# controller_board.net
KiCad netlist of a schematic drawn in EAGLE
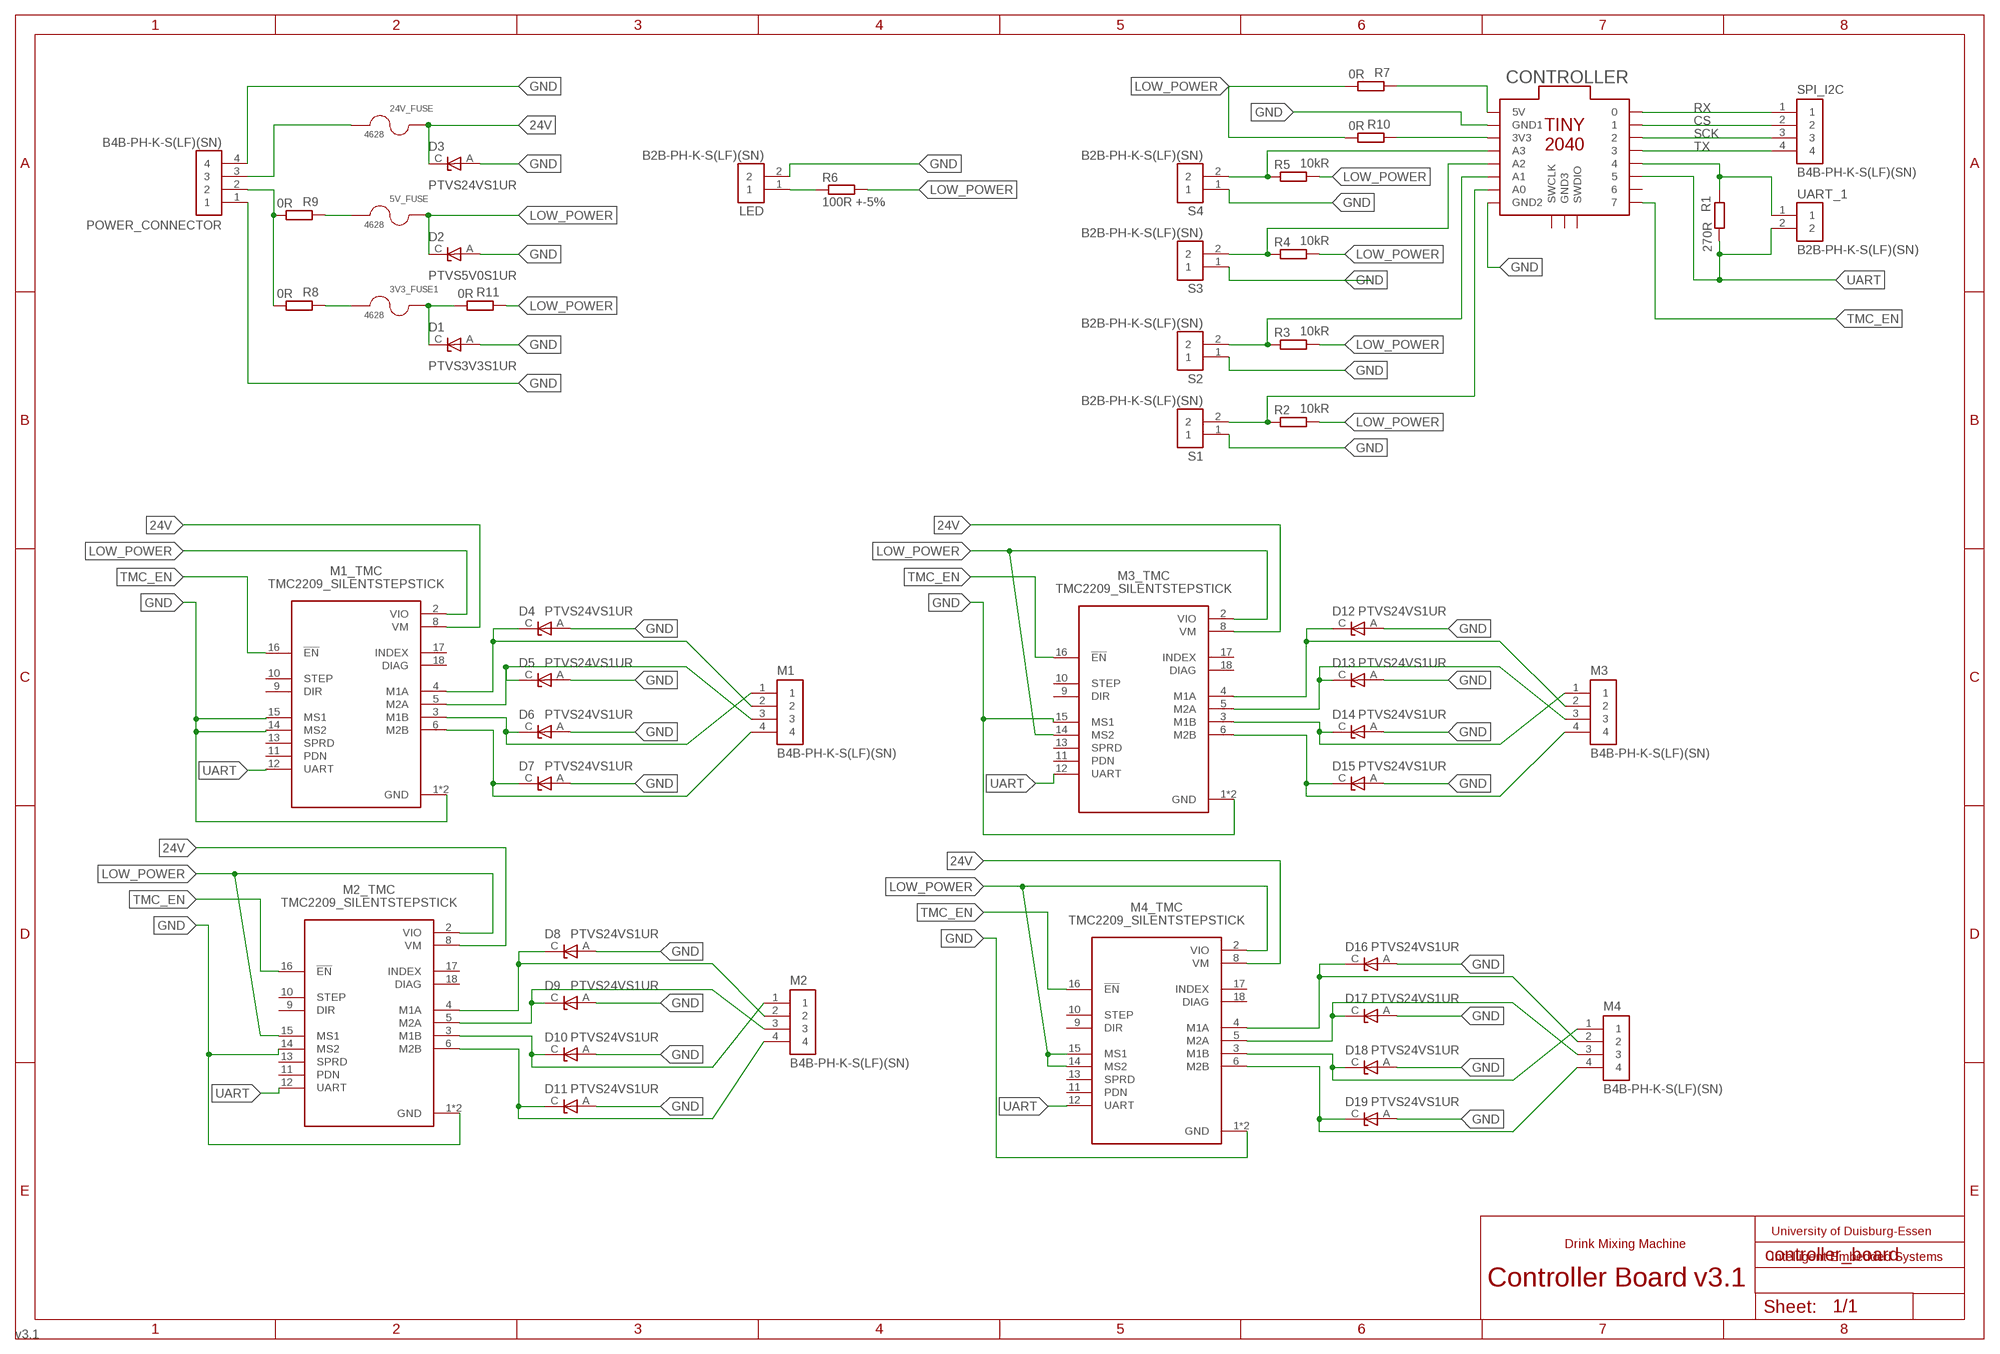
[diagram p0: schematic, sheet 1]

(export (version "E")
  (design (tool "Eeschema 10.0.6"))
  (components
    (comp (ref "3V3_FUSE1")
      (value "4628")
      (footprint "eagle-import:FUSE_4628")
      (fields (field (name "MF") "Keystone"))
      (libsource (lib "eagle-import") (part "4628"))
    )
    (comp (ref "5V_FUSE")
      (value "4628")
      (footprint "eagle-import:FUSE_4628")
      (fields (field (name "MF") "Keystone"))
      (libsource (lib "eagle-import") (part "4628"))
    )
    (comp (ref "24V_FUSE")
      (value "4628")
      (footprint "eagle-import:FUSE_4628")
      (fields (field (name "MF") "Keystone"))
      (libsource (lib "eagle-import") (part "4628"))
    )
    (comp (ref "CONTROLLER")
      (value "TINY2040_HEADER")
      (footprint "eagle-import:TINY2040_HEADER")
      (libsource (lib "eagle-import") (part "TINY2040_HEADER"))
    )
    (comp (ref "D1")
      (value "PTVS3V3S1UR")
      (footprint "eagle-import:TVS_PTVS3V3S1UR")
      (fields (field (name "MF") "Nexperia"))
      (libsource (lib "eagle-import") (part "PTVS3V3S1UR"))
    )
    (comp (ref "D2")
      (value "PTVS5V0S1UR")
      (footprint "eagle-import:TVS_PTVS5V0S1UR")
      (fields (field (name "MF") "Nexperia USA"))
      (libsource (lib "eagle-import") (part "PTVS5V0S1UR"))
    )
    (comp (ref "D3")
      (value "PTVS24VS1UR")
      (footprint "eagle-import:TVS_PTVS24VS1UR")
      (fields (field (name "MF") "Nexperia"))
      (libsource (lib "eagle-import") (part "PTVS24VS1UR"))
    )
    (comp (ref "D4")
      (value "PTVS24VS1UR")
      (footprint "eagle-import:TVS_PTVS24VS1UR")
      (fields (field (name "MF") "Nexperia"))
      (libsource (lib "eagle-import") (part "PTVS24VS1UR"))
    )
    (comp (ref "D5")
      (value "PTVS24VS1UR")
      (footprint "eagle-import:TVS_PTVS24VS1UR")
      (fields (field (name "MF") "Nexperia"))
      (libsource (lib "eagle-import") (part "PTVS24VS1UR"))
    )
    (comp (ref "D6")
      (value "PTVS24VS1UR")
      (footprint "eagle-import:TVS_PTVS24VS1UR")
      (fields (field (name "MF") "Nexperia"))
      (libsource (lib "eagle-import") (part "PTVS24VS1UR"))
    )
    (comp (ref "D7")
      (value "PTVS24VS1UR")
      (footprint "eagle-import:TVS_PTVS24VS1UR")
      (fields (field (name "MF") "Nexperia"))
      (libsource (lib "eagle-import") (part "PTVS24VS1UR"))
    )
    (comp (ref "D8")
      (value "PTVS24VS1UR")
      (footprint "eagle-import:TVS_PTVS24VS1UR")
      (fields (field (name "MF") "Nexperia"))
      (libsource (lib "eagle-import") (part "PTVS24VS1UR"))
    )
    (comp (ref "D9")
      (value "PTVS24VS1UR")
      (footprint "eagle-import:TVS_PTVS24VS1UR")
      (fields (field (name "MF") "Nexperia"))
      (libsource (lib "eagle-import") (part "PTVS24VS1UR"))
    )
    (comp (ref "D10")
      (value "PTVS24VS1UR")
      (footprint "eagle-import:TVS_PTVS24VS1UR")
      (fields (field (name "MF") "Nexperia"))
      (libsource (lib "eagle-import") (part "PTVS24VS1UR"))
    )
    (comp (ref "D11")
      (value "PTVS24VS1UR")
      (footprint "eagle-import:TVS_PTVS24VS1UR")
      (fields (field (name "MF") "Nexperia"))
      (libsource (lib "eagle-import") (part "PTVS24VS1UR"))
    )
    (comp (ref "D12")
      (value "PTVS24VS1UR")
      (footprint "eagle-import:TVS_PTVS24VS1UR")
      (fields (field (name "MF") "Nexperia"))
      (libsource (lib "eagle-import") (part "PTVS24VS1UR"))
    )
    (comp (ref "D13")
      (value "PTVS24VS1UR")
      (footprint "eagle-import:TVS_PTVS24VS1UR")
      (fields (field (name "MF") "Nexperia"))
      (libsource (lib "eagle-import") (part "PTVS24VS1UR"))
    )
    (comp (ref "D14")
      (value "PTVS24VS1UR")
      (footprint "eagle-import:TVS_PTVS24VS1UR")
      (fields (field (name "MF") "Nexperia"))
      (libsource (lib "eagle-import") (part "PTVS24VS1UR"))
    )
    (comp (ref "D15")
      (value "PTVS24VS1UR")
      (footprint "eagle-import:TVS_PTVS24VS1UR")
      (fields (field (name "MF") "Nexperia"))
      (libsource (lib "eagle-import") (part "PTVS24VS1UR"))
    )
    (comp (ref "D16")
      (value "PTVS24VS1UR")
      (footprint "eagle-import:TVS_PTVS24VS1UR")
      (fields (field (name "MF") "Nexperia"))
      (libsource (lib "eagle-import") (part "PTVS24VS1UR"))
    )
    (comp (ref "D17")
      (value "PTVS24VS1UR")
      (footprint "eagle-import:TVS_PTVS24VS1UR")
      (fields (field (name "MF") "Nexperia"))
      (libsource (lib "eagle-import") (part "PTVS24VS1UR"))
    )
    (comp (ref "D18")
      (value "PTVS24VS1UR")
      (footprint "eagle-import:TVS_PTVS24VS1UR")
      (fields (field (name "MF") "Nexperia"))
      (libsource (lib "eagle-import") (part "PTVS24VS1UR"))
    )
    (comp (ref "D19")
      (value "PTVS24VS1UR")
      (footprint "eagle-import:TVS_PTVS24VS1UR")
      (fields (field (name "MF") "Nexperia"))
      (libsource (lib "eagle-import") (part "PTVS24VS1UR"))
    )
    (comp (ref "LED")
      (value "B2B-PH-K-S(LF)(SN)")
      (footprint "eagle-import:JST_B2B-PH-K-S(LF)(SN)")
      (fields (field (name "MF") "JST") (field (name "MP") "B2B-PH-K-S (LF)(SN)"))
      (libsource (lib "eagle-import") (part "B2B-PH-K-S(LF)(SN)"))
    )
    (comp (ref "M1")
      (value "B4B-PH-K-S(LF)(SN)")
      (footprint "eagle-import:JST_B4B-PH-K-S(LF)(SN)")
      (fields (field (name "MF") "JST Sales"))
      (libsource (lib "eagle-import") (part "B4B-PH-K-S(LF)(SN)"))
    )
    (comp (ref "M1_TMC")
      (value "TMC2209_SILENTSTEPSTICK")
      (footprint "eagle-import:MODULE_TMC2209_SILENTSTEPSTICK")
      (fields
        (field (name "MF") "Trinamic Motion Control GmbH")
        (field (name "MP") "TMC2209 SILENTSTEPSTICK")
      )
      (libsource (lib "eagle-import") (part "TMC2209_SILENTSTEPSTICK"))
    )
    (comp (ref "M2")
      (value "B4B-PH-K-S(LF)(SN)")
      (footprint "eagle-import:JST_B4B-PH-K-S(LF)(SN)")
      (fields (field (name "MF") "JST Sales"))
      (libsource (lib "eagle-import") (part "B4B-PH-K-S(LF)(SN)"))
    )
    (comp (ref "M2_TMC")
      (value "TMC2209_SILENTSTEPSTICK")
      (footprint "eagle-import:MODULE_TMC2209_SILENTSTEPSTICK")
      (fields
        (field (name "MF") "Trinamic Motion Control GmbH")
        (field (name "MP") "TMC2209 SILENTSTEPSTICK")
      )
      (libsource (lib "eagle-import") (part "TMC2209_SILENTSTEPSTICK"))
    )
    (comp (ref "M3")
      (value "B4B-PH-K-S(LF)(SN)")
      (footprint "eagle-import:JST_B4B-PH-K-S(LF)(SN)")
      (fields (field (name "MF") "JST Sales"))
      (libsource (lib "eagle-import") (part "B4B-PH-K-S(LF)(SN)"))
    )
    (comp (ref "M3_TMC")
      (value "TMC2209_SILENTSTEPSTICK")
      (footprint "eagle-import:MODULE_TMC2209_SILENTSTEPSTICK")
      (fields
        (field (name "MF") "Trinamic Motion Control GmbH")
        (field (name "MP") "TMC2209 SILENTSTEPSTICK")
      )
      (libsource (lib "eagle-import") (part "TMC2209_SILENTSTEPSTICK"))
    )
    (comp (ref "M4")
      (value "B4B-PH-K-S(LF)(SN)")
      (footprint "eagle-import:JST_B4B-PH-K-S(LF)(SN)")
      (fields (field (name "MF") "JST Sales"))
      (libsource (lib "eagle-import") (part "B4B-PH-K-S(LF)(SN)"))
    )
    (comp (ref "M4_TMC")
      (value "TMC2209_SILENTSTEPSTICK")
      (footprint "eagle-import:MODULE_TMC2209_SILENTSTEPSTICK")
      (fields
        (field (name "MF") "Trinamic Motion Control GmbH")
        (field (name "MP") "TMC2209 SILENTSTEPSTICK")
      )
      (libsource (lib "eagle-import") (part "TMC2209_SILENTSTEPSTICK"))
    )
    (comp (ref "POWER_CONNECTOR")
      (value "B4B-PH-K-S(LF)(SN)")
      (footprint "eagle-import:JST_B4B-PH-K-S(LF)(SN)")
      (fields (field (name "MF") "JST Sales"))
      (libsource (lib "eagle-import") (part "B4B-PH-K-S(LF)(SN)"))
    )
    (comp (ref "R1")
      (value "270R")
      (footprint "eagle-import:R0805")
      (libsource (lib "eagle-import") (part "R-EU_R0805"))
    )
    (comp (ref "R2")
      (value "10kR")
      (footprint "eagle-import:R0805")
      (libsource (lib "eagle-import") (part "R-EU_R0805"))
    )
    (comp (ref "R3")
      (value "10kR")
      (footprint "eagle-import:R0805")
      (libsource (lib "eagle-import") (part "R-EU_R0805"))
    )
    (comp (ref "R4")
      (value "10kR")
      (footprint "eagle-import:R0805")
      (libsource (lib "eagle-import") (part "R-EU_R0805"))
    )
    (comp (ref "R5")
      (value "10kR")
      (footprint "eagle-import:R0805")
      (libsource (lib "eagle-import") (part "R-EU_R0805"))
    )
    (comp (ref "R6")
      (value "100R +-5%")
      (footprint "eagle-import:R0805")
      (libsource (lib "eagle-import") (part "R-EU_R0805"))
    )
    (comp (ref "R7")
      (value "0R")
      (footprint "eagle-import:R0805")
      (libsource (lib "eagle-import") (part "R-EU_R0805"))
    )
    (comp (ref "R8")
      (value "0R")
      (footprint "eagle-import:R0805")
      (libsource (lib "eagle-import") (part "R-EU_R0805"))
    )
    (comp (ref "R9")
      (value "0R")
      (footprint "eagle-import:R0805")
      (libsource (lib "eagle-import") (part "R-EU_R0805"))
    )
    (comp (ref "R10")
      (value "0R")
      (footprint "eagle-import:R0805")
      (libsource (lib "eagle-import") (part "R-EU_R0805"))
    )
    (comp (ref "R11")
      (value "0R")
      (footprint "eagle-import:R0805")
      (libsource (lib "eagle-import") (part "R-EU_R0805"))
    )
    (comp (ref "S1")
      (value "B2B-PH-K-S(LF)(SN)")
      (footprint "eagle-import:JST_B2B-PH-K-S(LF)(SN)")
      (fields (field (name "MF") "JST") (field (name "MP") "B2B-PH-K-S (LF)(SN)"))
      (libsource (lib "eagle-import") (part "B2B-PH-K-S(LF)(SN)"))
    )
    (comp (ref "S2")
      (value "B2B-PH-K-S(LF)(SN)")
      (footprint "eagle-import:JST_B2B-PH-K-S(LF)(SN)")
      (fields (field (name "MF") "JST") (field (name "MP") "B2B-PH-K-S (LF)(SN)"))
      (libsource (lib "eagle-import") (part "B2B-PH-K-S(LF)(SN)"))
    )
    (comp (ref "S3")
      (value "B2B-PH-K-S(LF)(SN)")
      (footprint "eagle-import:JST_B2B-PH-K-S(LF)(SN)")
      (fields (field (name "MF") "JST") (field (name "MP") "B2B-PH-K-S (LF)(SN)"))
      (libsource (lib "eagle-import") (part "B2B-PH-K-S(LF)(SN)"))
    )
    (comp (ref "S4")
      (value "B2B-PH-K-S(LF)(SN)")
      (footprint "eagle-import:JST_B2B-PH-K-S(LF)(SN)")
      (fields (field (name "MF") "JST") (field (name "MP") "B2B-PH-K-S (LF)(SN)"))
      (libsource (lib "eagle-import") (part "B2B-PH-K-S(LF)(SN)"))
    )
    (comp (ref "SPI_I2C")
      (value "B4B-PH-K-S(LF)(SN)")
      (footprint "eagle-import:JST_B4B-PH-K-S(LF)(SN)")
      (fields (field (name "MF") "JST Sales"))
      (libsource (lib "eagle-import") (part "B4B-PH-K-S(LF)(SN)"))
    )
    (comp (ref "UART_1")
      (value "B2B-PH-K-S(LF)(SN)")
      (footprint "eagle-import:JST_B2B-PH-K-S(LF)(SN)")
      (fields (field (name "MF") "JST") (field (name "MP") "B2B-PH-K-S (LF)(SN)"))
      (libsource (lib "eagle-import") (part "B2B-PH-K-S(LF)(SN)"))
    )
  )
  (nets
    (net (code "1") (name "/CS") (class "Default")
      (node (ref "CONTROLLER") (pin "1") (pinfunction "1_1") (pintype "bidirectional"))
      (node (ref "SPI_I2C") (pin "2") (pinfunction "2_2") (pintype "passive"))
    )
    (net (code "2") (name "/RX") (class "Default")
      (node (ref "CONTROLLER") (pin "0") (pinfunction "0_0") (pintype "bidirectional"))
      (node (ref "SPI_I2C") (pin "1") (pinfunction "1_1") (pintype "passive"))
    )
    (net (code "3") (name "/SCK") (class "Default")
      (node (ref "CONTROLLER") (pin "2") (pinfunction "2_2") (pintype "bidirectional"))
      (node (ref "SPI_I2C") (pin "3") (pinfunction "3_3") (pintype "passive"))
    )
    (net (code "4") (name "/TX") (class "Default")
      (node (ref "CONTROLLER") (pin "3") (pinfunction "3_3") (pintype "bidirectional"))
      (node (ref "SPI_I2C") (pin "4") (pinfunction "4_4") (pintype "passive"))
    )
    (net (code "5") (name "24V") (class "Default")
      (node (ref "24V_FUSE") (pin "2") (pinfunction "2_2") (pintype "passive"))
      (node (ref "D3") (pin "C") (pinfunction "C_C") (pintype "passive"))
      (node (ref "M1_TMC") (pin "8") (pinfunction "VM_8") (pintype "power_in"))
      (node (ref "M2_TMC") (pin "8") (pinfunction "VM_8") (pintype "power_in"))
      (node (ref "M3_TMC") (pin "8") (pinfunction "VM_8") (pintype "power_in"))
      (node (ref "M4_TMC") (pin "8") (pinfunction "VM_8") (pintype "power_in"))
    )
    (net (code "6") (name "GND") (class "Default")
      (node (ref "CONTROLLER") (pin "GND1") (pinfunction "GND1_GND1") (pintype "bidirectional"))
      (node (ref "CONTROLLER") (pin "GND2") (pinfunction "GND2_GND2") (pintype "bidirectional"))
      (node (ref "D1") (pin "A") (pinfunction "A_A") (pintype "passive"))
      (node (ref "D10") (pin "A") (pinfunction "A_A") (pintype "passive"))
      (node (ref "D11") (pin "A") (pinfunction "A_A") (pintype "passive"))
      (node (ref "D12") (pin "A") (pinfunction "A_A") (pintype "passive"))
      (node (ref "D13") (pin "A") (pinfunction "A_A") (pintype "passive"))
      (node (ref "D14") (pin "A") (pinfunction "A_A") (pintype "passive"))
      (node (ref "D15") (pin "A") (pinfunction "A_A") (pintype "passive"))
      (node (ref "D16") (pin "A") (pinfunction "A_A") (pintype "passive"))
      (node (ref "D17") (pin "A") (pinfunction "A_A") (pintype "passive"))
      (node (ref "D18") (pin "A") (pinfunction "A_A") (pintype "passive"))
      (node (ref "D19") (pin "A") (pinfunction "A_A") (pintype "passive"))
      (node (ref "D2") (pin "A") (pinfunction "A_A") (pintype "passive"))
      (node (ref "D3") (pin "A") (pinfunction "A_A") (pintype "passive"))
      (node (ref "D4") (pin "A") (pinfunction "A_A") (pintype "passive"))
      (node (ref "D5") (pin "A") (pinfunction "A_A") (pintype "passive"))
      (node (ref "D6") (pin "A") (pinfunction "A_A") (pintype "passive"))
      (node (ref "D7") (pin "A") (pinfunction "A_A") (pintype "passive"))
      (node (ref "D8") (pin "A") (pinfunction "A_A") (pintype "passive"))
      (node (ref "D9") (pin "A") (pinfunction "A_A") (pintype "passive"))
      (node (ref "LED") (pin "2") (pinfunction "2_2") (pintype "passive"))
      (node (ref "M1_TMC") (pin "1") (pinfunction "GND_1") (pintype "power_in"))
      (node (ref "M1_TMC") (pin "14") (pinfunction "MS2_14") (pintype "input"))
      (node (ref "M1_TMC") (pin "15") (pinfunction "MS1_15") (pintype "input"))
      (node (ref "M1_TMC") (pin "7") (pinfunction "GND_7") (pintype "power_in"))
      (node (ref "M2_TMC") (pin "1") (pinfunction "GND_1") (pintype "power_in"))
      (node (ref "M2_TMC") (pin "14") (pinfunction "MS2_14") (pintype "input"))
      (node (ref "M2_TMC") (pin "7") (pinfunction "GND_7") (pintype "power_in"))
      (node (ref "M3_TMC") (pin "1") (pinfunction "GND_1") (pintype "power_in"))
      (node (ref "M3_TMC") (pin "15") (pinfunction "MS1_15") (pintype "input"))
      (node (ref "M3_TMC") (pin "7") (pinfunction "GND_7") (pintype "power_in"))
      (node (ref "M4_TMC") (pin "1") (pinfunction "GND_1") (pintype "power_in"))
      (node (ref "M4_TMC") (pin "7") (pinfunction "GND_7") (pintype "power_in"))
      (node (ref "POWER_CONNECTOR") (pin "1") (pinfunction "1_1") (pintype "passive"))
      (node (ref "POWER_CONNECTOR") (pin "4") (pinfunction "4_4") (pintype "passive"))
      (node (ref "S1") (pin "1") (pinfunction "1_1") (pintype "passive"))
      (node (ref "S2") (pin "1") (pinfunction "1_1") (pintype "passive"))
      (node (ref "S3") (pin "1") (pinfunction "1_1") (pintype "passive"))
      (node (ref "S4") (pin "1") (pinfunction "1_1") (pintype "passive"))
    )
    (net (code "7") (name "LOW_POWER") (class "Default")
      (node (ref "5V_FUSE") (pin "2") (pinfunction "2_2") (pintype "passive"))
      (node (ref "D2") (pin "C") (pinfunction "C_C") (pintype "passive"))
      (node (ref "M1_TMC") (pin "2") (pinfunction "VIO_2") (pintype "power_in"))
      (node (ref "M2_TMC") (pin "15") (pinfunction "MS1_15") (pintype "input"))
      (node (ref "M2_TMC") (pin "2") (pinfunction "VIO_2") (pintype "power_in"))
      (node (ref "M3_TMC") (pin "14") (pinfunction "MS2_14") (pintype "input"))
      (node (ref "M3_TMC") (pin "2") (pinfunction "VIO_2") (pintype "power_in"))
      (node (ref "M4_TMC") (pin "14") (pinfunction "MS2_14") (pintype "input"))
      (node (ref "M4_TMC") (pin "15") (pinfunction "MS1_15") (pintype "input"))
      (node (ref "M4_TMC") (pin "2") (pinfunction "VIO_2") (pintype "power_in"))
      (node (ref "R10") (pin "2") (pinfunction "2_2") (pintype "passive"))
      (node (ref "R11") (pin "1") (pinfunction "1_1") (pintype "passive"))
      (node (ref "R2") (pin "2") (pinfunction "2_2") (pintype "passive"))
      (node (ref "R3") (pin "2") (pinfunction "2_2") (pintype "passive"))
      (node (ref "R4") (pin "2") (pinfunction "2_2") (pintype "passive"))
      (node (ref "R5") (pin "2") (pinfunction "2_2") (pintype "passive"))
      (node (ref "R6") (pin "2") (pinfunction "2_2") (pintype "passive"))
      (node (ref "R7") (pin "2") (pinfunction "2_2") (pintype "passive"))
    )
    (net (code "8") (name "Net-(3V3_FUSE1-Pad1)") (class "Default")
      (node (ref "3V3_FUSE1") (pin "1") (pinfunction "1_1") (pintype "passive"))
      (node (ref "R8") (pin "1") (pinfunction "1_1") (pintype "passive"))
    )
    (net (code "9") (name "Net-(3V3_FUSE1-Pad2)") (class "Default")
      (node (ref "3V3_FUSE1") (pin "2") (pinfunction "2_2") (pintype "passive"))
      (node (ref "D1") (pin "C") (pinfunction "C_C") (pintype "passive"))
      (node (ref "R11") (pin "2") (pinfunction "2_2") (pintype "passive"))
    )
    (net (code "10") (name "Net-(5V_FUSE-Pad1)") (class "Default")
      (node (ref "5V_FUSE") (pin "1") (pinfunction "1_1") (pintype "passive"))
      (node (ref "R9") (pin "1") (pinfunction "1_1") (pintype "passive"))
    )
    (net (code "11") (name "Net-(24V_FUSE-Pad1)") (class "Default")
      (node (ref "24V_FUSE") (pin "1") (pinfunction "1_1") (pintype "passive"))
      (node (ref "POWER_CONNECTOR") (pin "3") (pinfunction "3_3") (pintype "passive"))
    )
    (net (code "12") (name "Net-(CONTROLLER-Pad3V3)") (class "Default")
      (node (ref "CONTROLLER") (pin "3V3") (pinfunction "3V3_3V3") (pintype "bidirectional"))
      (node (ref "R10") (pin "1") (pinfunction "1_1") (pintype "passive"))
    )
    (net (code "13") (name "Net-(CONTROLLER-Pad4)") (class "Default")
      (node (ref "CONTROLLER") (pin "4") (pinfunction "4_4") (pintype "bidirectional"))
      (node (ref "R1") (pin "1") (pinfunction "1_1") (pintype "passive"))
      (node (ref "UART_1") (pin "1") (pinfunction "1_1") (pintype "passive"))
    )
    (net (code "14") (name "Net-(CONTROLLER-Pad5V)") (class "Default")
      (node (ref "CONTROLLER") (pin "5V") (pinfunction "5V_5V") (pintype "bidirectional"))
      (node (ref "R7") (pin "1") (pinfunction "1_1") (pintype "passive"))
    )
    (net (code "15") (name "Net-(CONTROLLER-PadA0)") (class "Default")
      (node (ref "CONTROLLER") (pin "A0") (pinfunction "A0_A0") (pintype "bidirectional"))
      (node (ref "R2") (pin "1") (pinfunction "1_1") (pintype "passive"))
      (node (ref "S1") (pin "2") (pinfunction "2_2") (pintype "passive"))
    )
    (net (code "16") (name "Net-(CONTROLLER-PadA1)") (class "Default")
      (node (ref "CONTROLLER") (pin "A1") (pinfunction "A1_A1") (pintype "bidirectional"))
      (node (ref "R3") (pin "1") (pinfunction "1_1") (pintype "passive"))
      (node (ref "S2") (pin "2") (pinfunction "2_2") (pintype "passive"))
    )
    (net (code "17") (name "Net-(CONTROLLER-PadA2)") (class "Default")
      (node (ref "CONTROLLER") (pin "A2") (pinfunction "A2_A2") (pintype "bidirectional"))
      (node (ref "R4") (pin "1") (pinfunction "1_1") (pintype "passive"))
      (node (ref "S3") (pin "2") (pinfunction "2_2") (pintype "passive"))
    )
    (net (code "18") (name "Net-(CONTROLLER-PadA3)") (class "Default")
      (node (ref "CONTROLLER") (pin "A3") (pinfunction "A3_A3") (pintype "bidirectional"))
      (node (ref "R5") (pin "1") (pinfunction "1_1") (pintype "passive"))
      (node (ref "S4") (pin "2") (pinfunction "2_2") (pintype "passive"))
    )
    (net (code "19") (name "Net-(LED-Pad1)") (class "Default")
      (node (ref "LED") (pin "1") (pinfunction "1_1") (pintype "passive"))
      (node (ref "R6") (pin "1") (pinfunction "1_1") (pintype "passive"))
    )
    (net (code "20") (name "Net-(M1_TMC-M1A)") (class "Default")
      (node (ref "D4") (pin "C") (pinfunction "C_C") (pintype "passive"))
      (node (ref "M1") (pin "2") (pinfunction "2_2") (pintype "passive"))
      (node (ref "M1_TMC") (pin "4") (pinfunction "M1A_4") (pintype "output"))
    )
    (net (code "21") (name "Net-(M1_TMC-M1B)") (class "Default")
      (node (ref "D6") (pin "C") (pinfunction "C_C") (pintype "passive"))
      (node (ref "M1") (pin "1") (pinfunction "1_1") (pintype "passive"))
      (node (ref "M1_TMC") (pin "3") (pinfunction "M1B_3") (pintype "output"))
    )
    (net (code "22") (name "Net-(M1_TMC-M2A)") (class "Default")
      (node (ref "D5") (pin "C") (pinfunction "C_C") (pintype "passive"))
      (node (ref "M1") (pin "3") (pinfunction "3_3") (pintype "passive"))
      (node (ref "M1_TMC") (pin "5") (pinfunction "M2A_5") (pintype "output"))
    )
    (net (code "23") (name "Net-(M1_TMC-M2B)") (class "Default")
      (node (ref "D7") (pin "C") (pinfunction "C_C") (pintype "passive"))
      (node (ref "M1") (pin "4") (pinfunction "4_4") (pintype "passive"))
      (node (ref "M1_TMC") (pin "6") (pinfunction "M2B_6") (pintype "output"))
    )
    (net (code "24") (name "Net-(M2_TMC-M1A)") (class "Default")
      (node (ref "D8") (pin "C") (pinfunction "C_C") (pintype "passive"))
      (node (ref "M2") (pin "2") (pinfunction "2_2") (pintype "passive"))
      (node (ref "M2_TMC") (pin "4") (pinfunction "M1A_4") (pintype "output"))
    )
    (net (code "25") (name "Net-(M2_TMC-M1B)") (class "Default")
      (node (ref "D10") (pin "C") (pinfunction "C_C") (pintype "passive"))
      (node (ref "M2") (pin "1") (pinfunction "1_1") (pintype "passive"))
      (node (ref "M2_TMC") (pin "3") (pinfunction "M1B_3") (pintype "output"))
    )
    (net (code "26") (name "Net-(M2_TMC-M2A)") (class "Default")
      (node (ref "D9") (pin "C") (pinfunction "C_C") (pintype "passive"))
      (node (ref "M2") (pin "3") (pinfunction "3_3") (pintype "passive"))
      (node (ref "M2_TMC") (pin "5") (pinfunction "M2A_5") (pintype "output"))
    )
    (net (code "27") (name "Net-(M2_TMC-M2B)") (class "Default")
      (node (ref "D11") (pin "C") (pinfunction "C_C") (pintype "passive"))
      (node (ref "M2") (pin "4") (pinfunction "4_4") (pintype "passive"))
      (node (ref "M2_TMC") (pin "6") (pinfunction "M2B_6") (pintype "output"))
    )
    (net (code "28") (name "Net-(M3_TMC-M1A)") (class "Default")
      (node (ref "D12") (pin "C") (pinfunction "C_C") (pintype "passive"))
      (node (ref "M3") (pin "2") (pinfunction "2_2") (pintype "passive"))
      (node (ref "M3_TMC") (pin "4") (pinfunction "M1A_4") (pintype "output"))
    )
    (net (code "29") (name "Net-(M3_TMC-M1B)") (class "Default")
      (node (ref "D14") (pin "C") (pinfunction "C_C") (pintype "passive"))
      (node (ref "M3") (pin "1") (pinfunction "1_1") (pintype "passive"))
      (node (ref "M3_TMC") (pin "3") (pinfunction "M1B_3") (pintype "output"))
    )
    (net (code "30") (name "Net-(M3_TMC-M2A)") (class "Default")
      (node (ref "D13") (pin "C") (pinfunction "C_C") (pintype "passive"))
      (node (ref "M3") (pin "3") (pinfunction "3_3") (pintype "passive"))
      (node (ref "M3_TMC") (pin "5") (pinfunction "M2A_5") (pintype "output"))
    )
    (net (code "31") (name "Net-(M3_TMC-M2B)") (class "Default")
      (node (ref "D15") (pin "C") (pinfunction "C_C") (pintype "passive"))
      (node (ref "M3") (pin "4") (pinfunction "4_4") (pintype "passive"))
      (node (ref "M3_TMC") (pin "6") (pinfunction "M2B_6") (pintype "output"))
    )
    (net (code "32") (name "Net-(M4_TMC-M1A)") (class "Default")
      (node (ref "D16") (pin "C") (pinfunction "C_C") (pintype "passive"))
      (node (ref "M4") (pin "2") (pinfunction "2_2") (pintype "passive"))
      (node (ref "M4_TMC") (pin "4") (pinfunction "M1A_4") (pintype "output"))
    )
    (net (code "33") (name "Net-(M4_TMC-M1B)") (class "Default")
      (node (ref "D18") (pin "C") (pinfunction "C_C") (pintype "passive"))
      (node (ref "M4") (pin "1") (pinfunction "1_1") (pintype "passive"))
      (node (ref "M4_TMC") (pin "3") (pinfunction "M1B_3") (pintype "output"))
    )
    (net (code "34") (name "Net-(M4_TMC-M2A)") (class "Default")
      (node (ref "D17") (pin "C") (pinfunction "C_C") (pintype "passive"))
      (node (ref "M4") (pin "3") (pinfunction "3_3") (pintype "passive"))
      (node (ref "M4_TMC") (pin "5") (pinfunction "M2A_5") (pintype "output"))
    )
    (net (code "35") (name "Net-(M4_TMC-M2B)") (class "Default")
      (node (ref "D19") (pin "C") (pinfunction "C_C") (pintype "passive"))
      (node (ref "M4") (pin "4") (pinfunction "4_4") (pintype "passive"))
      (node (ref "M4_TMC") (pin "6") (pinfunction "M2B_6") (pintype "output"))
    )
    (net (code "36") (name "Net-(POWER_CONNECTOR-Pad2)") (class "Default")
      (node (ref "POWER_CONNECTOR") (pin "2") (pinfunction "2_2") (pintype "passive"))
      (node (ref "R8") (pin "2") (pinfunction "2_2") (pintype "passive"))
      (node (ref "R9") (pin "2") (pinfunction "2_2") (pintype "passive"))
    )
    (net (code "37") (name "TMC_EN") (class "Default")
      (node (ref "CONTROLLER") (pin "7") (pinfunction "7_7") (pintype "bidirectional"))
      (node (ref "M1_TMC") (pin "16") (pinfunction "~{EN}_16") (pintype "input"))
      (node (ref "M2_TMC") (pin "16") (pinfunction "~{EN}_16") (pintype "input"))
      (node (ref "M3_TMC") (pin "16") (pinfunction "~{EN}_16") (pintype "input"))
      (node (ref "M4_TMC") (pin "16") (pinfunction "~{EN}_16") (pintype "input"))
    )
    (net (code "38") (name "UART") (class "Default")
      (node (ref "CONTROLLER") (pin "5") (pinfunction "5_5") (pintype "bidirectional"))
      (node (ref "M1_TMC") (pin "12") (pinfunction "UART_12") (pintype "bidirectional"))
      (node (ref "M2_TMC") (pin "12") (pinfunction "UART_12") (pintype "bidirectional"))
      (node (ref "M3_TMC") (pin "12") (pinfunction "UART_12") (pintype "bidirectional"))
      (node (ref "M4_TMC") (pin "12") (pinfunction "UART_12") (pintype "bidirectional"))
      (node (ref "R1") (pin "2") (pinfunction "2_2") (pintype "passive"))
      (node (ref "UART_1") (pin "2") (pinfunction "2_2") (pintype "passive"))
    )
    (net (code "39") (name "unconnected-(CONTROLLER-Pad6)") (class "Default")
      (node (ref "CONTROLLER") (pin "6") (pinfunction "6_6") (pintype "bidirectional"))
    )
    (net (code "40") (name "unconnected-(CONTROLLER-PadGND3)") (class "Default")
      (node (ref "CONTROLLER") (pin "GND3") (pinfunction "GND3_GND3") (pintype "bidirectional"))
    )
    (net (code "41") (name "unconnected-(CONTROLLER-PadSWCLK)") (class "Default")
      (node (ref "CONTROLLER") (pin "SWCLK") (pinfunction "SWCLK_SWCLK") (pintype "bidirectional"))
    )
    (net (code "42") (name "unconnected-(CONTROLLER-PadSWDIO)") (class "Default")
      (node (ref "CONTROLLER") (pin "SWDIO") (pinfunction "SWDIO_SWDIO") (pintype "bidirectional"))
    )
    (net (code "43") (name "unconnected-(M1_TMC-DIAG-Pad18)") (class "Default")
      (node (ref "M1_TMC") (pin "18") (pinfunction "DIAG_18") (pintype "output"))
    )
    (net (code "44") (name "unconnected-(M1_TMC-DIR-Pad9)") (class "Default")
      (node (ref "M1_TMC") (pin "9") (pinfunction "DIR_9") (pintype "input"))
    )
    (net (code "45") (name "unconnected-(M1_TMC-INDEX-Pad17)") (class "Default")
      (node (ref "M1_TMC") (pin "17") (pinfunction "INDEX_17") (pintype "output"))
    )
    (net (code "46") (name "unconnected-(M1_TMC-PDN-Pad11)") (class "Default")
      (node (ref "M1_TMC") (pin "11") (pinfunction "PDN_11") (pintype "bidirectional"))
    )
    (net (code "47") (name "unconnected-(M1_TMC-SPRD-Pad13)") (class "Default")
      (node (ref "M1_TMC") (pin "13") (pinfunction "SPRD_13") (pintype "input"))
    )
    (net (code "48") (name "unconnected-(M1_TMC-STEP-Pad10)") (class "Default")
      (node (ref "M1_TMC") (pin "10") (pinfunction "STEP_10") (pintype "input"))
    )
    (net (code "49") (name "unconnected-(M2_TMC-DIAG-Pad18)") (class "Default")
      (node (ref "M2_TMC") (pin "18") (pinfunction "DIAG_18") (pintype "output"))
    )
    (net (code "50") (name "unconnected-(M2_TMC-DIR-Pad9)") (class "Default")
      (node (ref "M2_TMC") (pin "9") (pinfunction "DIR_9") (pintype "input"))
    )
    (net (code "51") (name "unconnected-(M2_TMC-INDEX-Pad17)") (class "Default")
      (node (ref "M2_TMC") (pin "17") (pinfunction "INDEX_17") (pintype "output"))
    )
    (net (code "52") (name "unconnected-(M2_TMC-PDN-Pad11)") (class "Default")
      (node (ref "M2_TMC") (pin "11") (pinfunction "PDN_11") (pintype "bidirectional"))
    )
    (net (code "53") (name "unconnected-(M2_TMC-SPRD-Pad13)") (class "Default")
      (node (ref "M2_TMC") (pin "13") (pinfunction "SPRD_13") (pintype "input"))
    )
    (net (code "54") (name "unconnected-(M2_TMC-STEP-Pad10)") (class "Default")
      (node (ref "M2_TMC") (pin "10") (pinfunction "STEP_10") (pintype "input"))
    )
    (net (code "55") (name "unconnected-(M3_TMC-DIAG-Pad18)") (class "Default")
      (node (ref "M3_TMC") (pin "18") (pinfunction "DIAG_18") (pintype "output"))
    )
    (net (code "56") (name "unconnected-(M3_TMC-DIR-Pad9)") (class "Default")
      (node (ref "M3_TMC") (pin "9") (pinfunction "DIR_9") (pintype "input"))
    )
    (net (code "57") (name "unconnected-(M3_TMC-INDEX-Pad17)") (class "Default")
      (node (ref "M3_TMC") (pin "17") (pinfunction "INDEX_17") (pintype "output"))
    )
    (net (code "58") (name "unconnected-(M3_TMC-PDN-Pad11)") (class "Default")
      (node (ref "M3_TMC") (pin "11") (pinfunction "PDN_11") (pintype "bidirectional"))
    )
    (net (code "59") (name "unconnected-(M3_TMC-SPRD-Pad13)") (class "Default")
      (node (ref "M3_TMC") (pin "13") (pinfunction "SPRD_13") (pintype "input"))
    )
    (net (code "60") (name "unconnected-(M3_TMC-STEP-Pad10)") (class "Default")
      (node (ref "M3_TMC") (pin "10") (pinfunction "STEP_10") (pintype "input"))
    )
    (net (code "61") (name "unconnected-(M4_TMC-DIAG-Pad18)") (class "Default")
      (node (ref "M4_TMC") (pin "18") (pinfunction "DIAG_18") (pintype "output"))
    )
    (net (code "62") (name "unconnected-(M4_TMC-DIR-Pad9)") (class "Default")
      (node (ref "M4_TMC") (pin "9") (pinfunction "DIR_9") (pintype "input"))
    )
    (net (code "63") (name "unconnected-(M4_TMC-INDEX-Pad17)") (class "Default")
      (node (ref "M4_TMC") (pin "17") (pinfunction "INDEX_17") (pintype "output"))
    )
    (net (code "64") (name "unconnected-(M4_TMC-PDN-Pad11)") (class "Default")
      (node (ref "M4_TMC") (pin "11") (pinfunction "PDN_11") (pintype "bidirectional"))
    )
    (net (code "65") (name "unconnected-(M4_TMC-SPRD-Pad13)") (class "Default")
      (node (ref "M4_TMC") (pin "13") (pinfunction "SPRD_13") (pintype "input"))
    )
    (net (code "66") (name "unconnected-(M4_TMC-STEP-Pad10)") (class "Default")
      (node (ref "M4_TMC") (pin "10") (pinfunction "STEP_10") (pintype "input"))
    )
  )
)
